# BahceKontrol.net
KiCad netlist of a schematic drawn in EAGLE
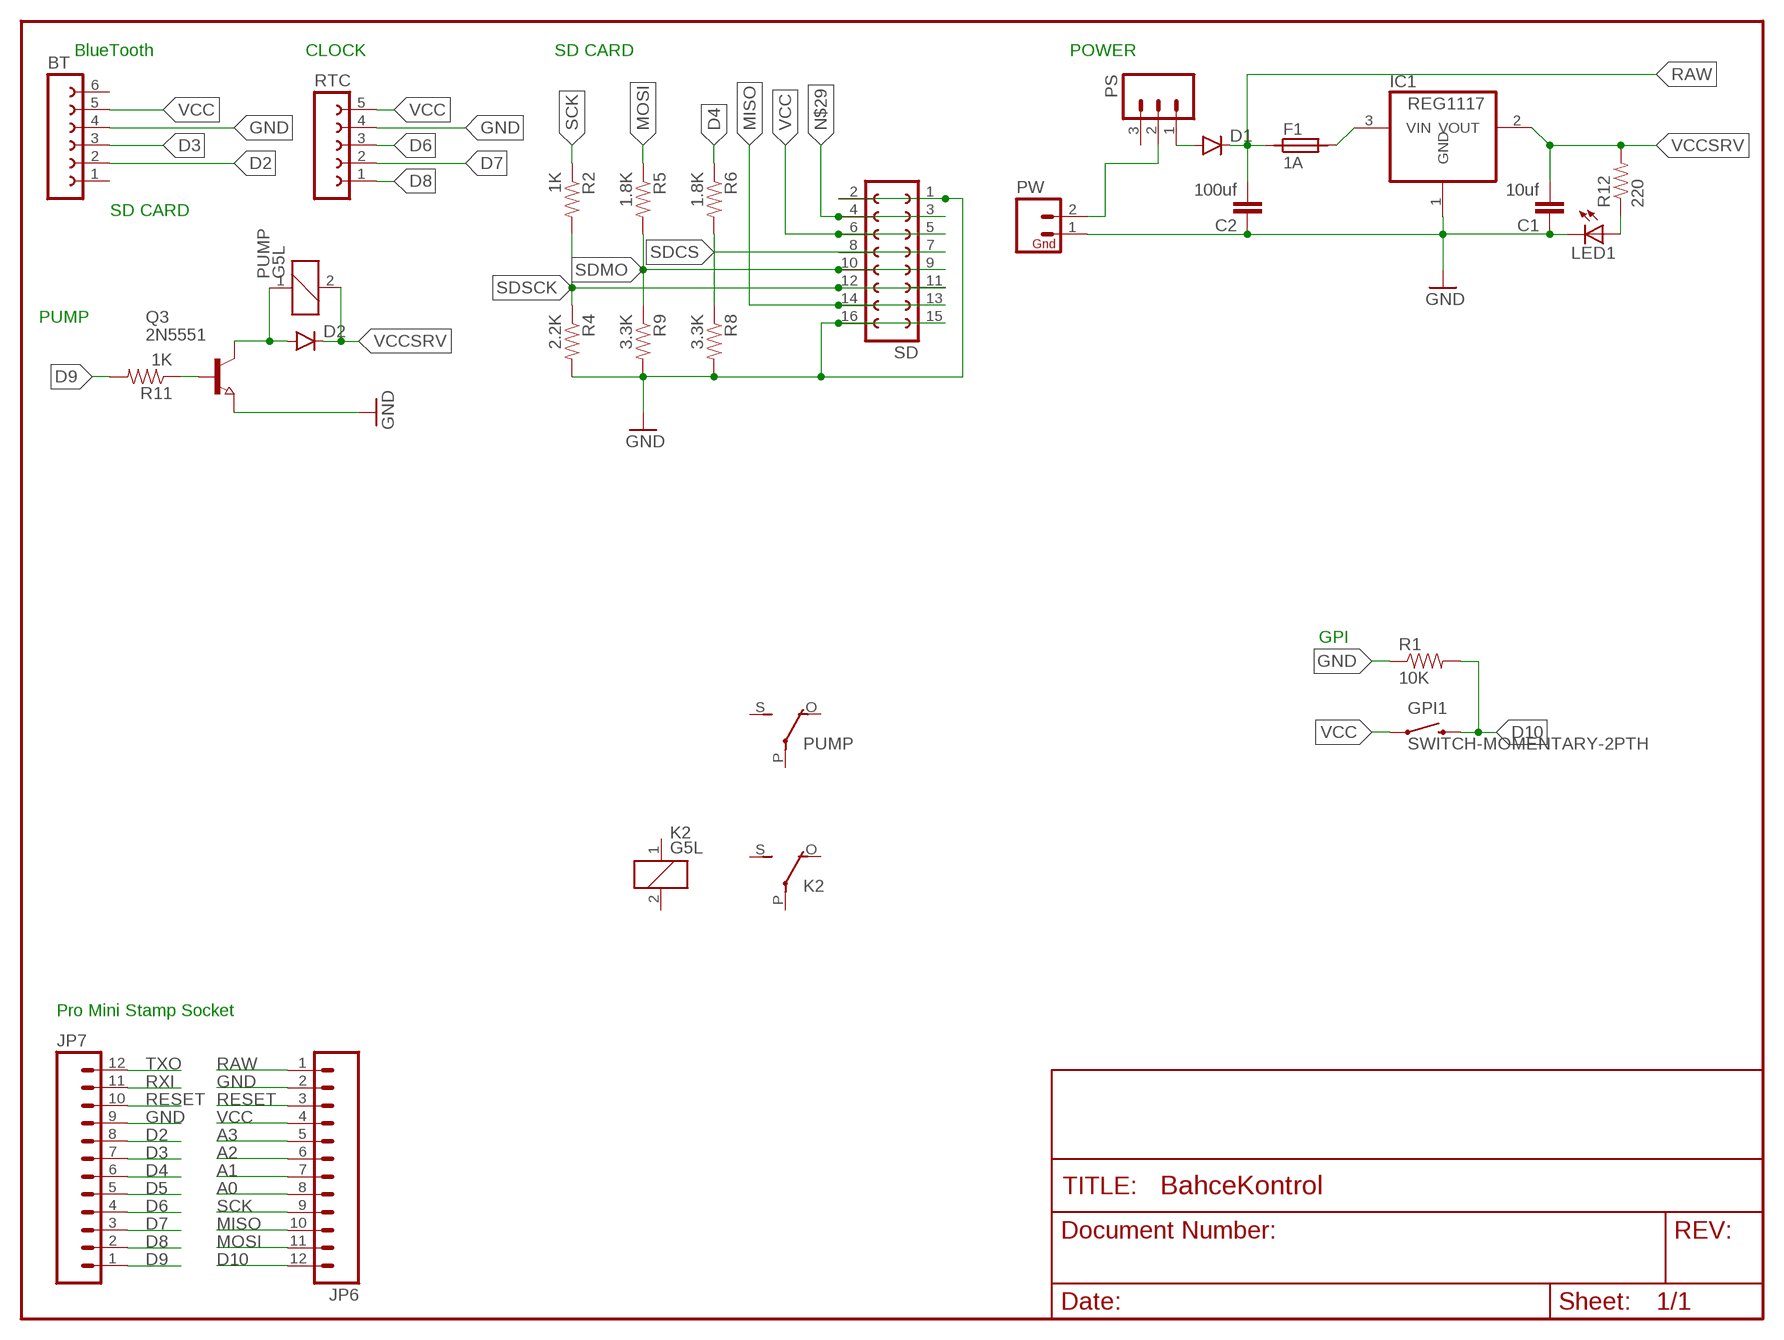
[diagram p0: schematic, sheet 1]

(export (version "E")
  (design (tool "Eeschema 10.0.6"))
  (components
    (comp (ref "BT")
      (value "FE06-1")
      (footprint "eagle-import:FE06")
      (libsource (lib "eagle-import") (part "FE06-1"))
    )
    (comp (ref "C1")
      (value "10uf")
      (footprint "eagle-import:0805")
      (libsource (lib "eagle-import") (part "CAP0805"))
    )
    (comp (ref "C2")
      (value "100uf")
      (footprint "eagle-import:0805")
      (libsource (lib "eagle-import") (part "CAP0805"))
    )
    (comp (ref "D1")
      (value "DIODESMA")
      (footprint "eagle-import:SMA-DIODE")
      (libsource (lib "eagle-import") (part "DIODESMA"))
    )
    (comp (ref "D2")
      (value "DIODESMA")
      (footprint "eagle-import:SMA-DIODE")
      (libsource (lib "eagle-import") (part "DIODESMA"))
    )
    (comp (ref "F1")
      (value "1A")
      (footprint "eagle-import:1820")
      (libsource (lib "eagle-import") (part "SIBA194600"))
    )
    (comp (ref "GPI1")
      (value "SWITCH-MOMENTARY-2PTH")
      (footprint "eagle-import:TACTILE-PTH")
      (libsource (lib "eagle-import") (part "SWITCH-MOMENTARY-2PTH"))
    )
    (comp (ref "IC1")
      (value "REG1117")
      (footprint "eagle-import:SOT223")
      (libsource (lib "eagle-import") (part "REG1117"))
    )
    (comp (ref "JP6")
      (value "M12PTH")
      (footprint "eagle-import:1X12")
      (libsource (lib "eagle-import") (part "M12PTH"))
    )
    (comp (ref "JP7")
      (value "M12PTH")
      (footprint "eagle-import:1X12")
      (libsource (lib "eagle-import") (part "M12PTH"))
    )
    (comp (ref "K2")
      (value "G5L")
      (footprint "eagle-import:G5LE")
      (libsource (lib "eagle-import") (part "G5L"))
    )
    (comp (ref "LED1")
      (value "LEDCHIP-LED0805")
      (footprint "eagle-import:CHIP-LED0805")
      (libsource (lib "eagle-import") (part "LEDCHIP-LED0805"))
    )
    (comp (ref "PS")
      (value "M03PTH")
      (footprint "eagle-import:1X03")
      (libsource (lib "eagle-import") (part "M03PTH"))
    )
    (comp (ref "PUMP")
      (value "G5L")
      (footprint "eagle-import:G5LE")
      (libsource (lib "eagle-import") (part "G5L"))
    )
    (comp (ref "PW")
      (value "M02PTH")
      (footprint "eagle-import:1X02")
      (libsource (lib "eagle-import") (part "M02PTH"))
    )
    (comp (ref "Q3")
      (value "2N5551")
      (footprint "eagle-import:SOT23")
      (libsource (lib "eagle-import") (part "NPN-TRANSISTOR_SOT23"))
    )
    (comp (ref "R1")
      (value "10K")
      (footprint "eagle-import:0805")
      (libsource (lib "eagle-import") (part "RESISTOR0805-RES"))
    )
    (comp (ref "R2")
      (value "1K")
      (footprint "eagle-import:0805")
      (libsource (lib "eagle-import") (part "RESISTOR0805-RES"))
    )
    (comp (ref "R4")
      (value "2.2K")
      (footprint "eagle-import:0805")
      (libsource (lib "eagle-import") (part "RESISTOR0805-RES"))
    )
    (comp (ref "R5")
      (value "1.8K")
      (footprint "eagle-import:0805")
      (libsource (lib "eagle-import") (part "RESISTOR0805-RES"))
    )
    (comp (ref "R6")
      (value "1.8K")
      (footprint "eagle-import:0805")
      (libsource (lib "eagle-import") (part "RESISTOR0805-RES"))
    )
    (comp (ref "R8")
      (value "3.3K")
      (footprint "eagle-import:0805")
      (libsource (lib "eagle-import") (part "RESISTOR0805-RES"))
    )
    (comp (ref "R9")
      (value "3.3K")
      (footprint "eagle-import:0805")
      (libsource (lib "eagle-import") (part "RESISTOR0805-RES"))
    )
    (comp (ref "R11")
      (value "1K")
      (footprint "eagle-import:0805")
      (libsource (lib "eagle-import") (part "RESISTOR0805-RES"))
    )
    (comp (ref "R12")
      (value "220")
      (footprint "eagle-import:0805")
      (libsource (lib "eagle-import") (part "RESISTOR0805-RES"))
    )
    (comp (ref "RTC")
      (value "FE05-1")
      (footprint "eagle-import:FE05-1")
      (libsource (lib "eagle-import") (part "FE05-1"))
    )
    (comp (ref "SD")
      (value "FE08-2")
      (footprint "eagle-import:FE08-2")
      (libsource (lib "eagle-import") (part "FE08-2"))
    )
  )
  (nets
    (net (code "1") (name "/A0") (class "Default")
      (node (ref "JP6") (pin "8") (pinfunction "8_8") (pintype "passive"))
    )
    (net (code "2") (name "/A1") (class "Default")
      (node (ref "JP6") (pin "7") (pinfunction "7_7") (pintype "passive"))
    )
    (net (code "3") (name "/A2") (class "Default")
      (node (ref "JP6") (pin "6") (pinfunction "6_6") (pintype "passive"))
    )
    (net (code "4") (name "/A3") (class "Default")
      (node (ref "JP6") (pin "5") (pinfunction "5_5") (pintype "passive"))
    )
    (net (code "5") (name "/D5") (class "Default")
      (node (ref "JP7") (pin "5") (pinfunction "5_5") (pintype "passive"))
    )
    (net (code "6") (name "/RESET") (class "Default")
      (node (ref "JP6") (pin "3") (pinfunction "3_3") (pintype "passive"))
      (node (ref "JP7") (pin "10") (pinfunction "10_10") (pintype "passive"))
    )
    (net (code "7") (name "/RXI") (class "Default")
      (node (ref "JP7") (pin "11") (pinfunction "11_11") (pintype "passive"))
    )
    (net (code "8") (name "/TXO") (class "Default")
      (node (ref "JP7") (pin "12") (pinfunction "12_12") (pintype "passive"))
    )
    (net (code "9") (name "D2") (class "Default")
      (node (ref "BT") (pin "2") (pinfunction "2_2") (pintype "passive"))
      (node (ref "JP7") (pin "8") (pinfunction "8_8") (pintype "passive"))
    )
    (net (code "10") (name "D3") (class "Default")
      (node (ref "BT") (pin "3") (pinfunction "3_3") (pintype "passive"))
      (node (ref "JP7") (pin "7") (pinfunction "7_7") (pintype "passive"))
    )
    (net (code "11") (name "D4") (class "Default")
      (node (ref "JP7") (pin "6") (pinfunction "6_6") (pintype "passive"))
      (node (ref "R6") (pin "1") (pinfunction "1_1") (pintype "passive"))
    )
    (net (code "12") (name "D6") (class "Default")
      (node (ref "JP7") (pin "4") (pinfunction "4_4") (pintype "passive"))
      (node (ref "RTC") (pin "3") (pinfunction "3_3") (pintype "passive"))
    )
    (net (code "13") (name "D7") (class "Default")
      (node (ref "JP7") (pin "3") (pinfunction "3_3") (pintype "passive"))
      (node (ref "RTC") (pin "2") (pinfunction "2_2") (pintype "passive"))
    )
    (net (code "14") (name "D8") (class "Default")
      (node (ref "JP7") (pin "2") (pinfunction "2_2") (pintype "passive"))
      (node (ref "RTC") (pin "1") (pinfunction "1_1") (pintype "passive"))
    )
    (net (code "15") (name "D9") (class "Default")
      (node (ref "JP7") (pin "1") (pinfunction "1_1") (pintype "passive"))
      (node (ref "R11") (pin "2") (pinfunction "2_2") (pintype "passive"))
    )
    (net (code "16") (name "D10") (class "Default")
      (node (ref "GPI1") (pin "3") (pinfunction "2_3") (pintype "passive"))
      (node (ref "JP6") (pin "12") (pinfunction "12_12") (pintype "passive"))
      (node (ref "R1") (pin "2") (pinfunction "2_2") (pintype "passive"))
    )
    (net (code "17") (name "GND") (class "Default")
      (node (ref "BT") (pin "4") (pinfunction "4_4") (pintype "passive"))
      (node (ref "C1") (pin "1") (pinfunction "1_1") (pintype "passive"))
      (node (ref "C2") (pin "1") (pinfunction "1_1") (pintype "passive"))
      (node (ref "IC1") (pin "1") (pinfunction "GND_1") (pintype "power_in"))
      (node (ref "JP6") (pin "2") (pinfunction "2_2") (pintype "passive"))
      (node (ref "JP7") (pin "9") (pinfunction "9_9") (pintype "passive"))
      (node (ref "LED1") (pin "C") (pinfunction "C_C") (pintype "passive"))
      (node (ref "PW") (pin "1") (pinfunction "1_1") (pintype "passive"))
      (node (ref "Q3") (pin "2") (pinfunction "E_2") (pintype "passive"))
      (node (ref "R1") (pin "1") (pinfunction "1_1") (pintype "passive"))
      (node (ref "R4") (pin "2") (pinfunction "2_2") (pintype "passive"))
      (node (ref "R8") (pin "2") (pinfunction "2_2") (pintype "passive"))
      (node (ref "R9") (pin "2") (pinfunction "2_2") (pintype "passive"))
      (node (ref "RTC") (pin "4") (pinfunction "4_4") (pintype "passive"))
      (node (ref "SD") (pin "1") (pinfunction "1_1") (pintype "passive"))
      (node (ref "SD") (pin "15") (pinfunction "15_15") (pintype "passive"))
      (node (ref "SD") (pin "16") (pinfunction "16_16") (pintype "passive"))
      (node (ref "SD") (pin "2") (pinfunction "2_2") (pintype "passive"))
    )
    (net (code "18") (name "MISO") (class "Default")
      (node (ref "JP6") (pin "10") (pinfunction "10_10") (pintype "passive"))
      (node (ref "SD") (pin "13") (pinfunction "13_13") (pintype "passive"))
      (node (ref "SD") (pin "14") (pinfunction "14_14") (pintype "passive"))
    )
    (net (code "19") (name "MOSI") (class "Default")
      (node (ref "JP6") (pin "11") (pinfunction "11_11") (pintype "passive"))
      (node (ref "R5") (pin "1") (pinfunction "1_1") (pintype "passive"))
    )
    (net (code "20") (name "N$29") (class "Default")
      (node (ref "SD") (pin "3") (pinfunction "3_3") (pintype "passive"))
      (node (ref "SD") (pin "4") (pinfunction "4_4") (pintype "passive"))
    )
    (net (code "21") (name "Net-(D1-PadA)") (class "Default")
      (node (ref "D1") (pin "A") (pinfunction "A_A") (pintype "passive"))
      (node (ref "PS") (pin "1") (pinfunction "1_1") (pintype "passive"))
    )
    (net (code "22") (name "Net-(IC1-VIN)") (class "Default")
      (node (ref "F1") (pin "2") (pinfunction "2_2") (pintype "passive"))
      (node (ref "IC1") (pin "3") (pinfunction "VIN_3") (pintype "input"))
    )
    (net (code "23") (name "Net-(LED1-PadA)") (class "Default")
      (node (ref "LED1") (pin "A") (pinfunction "A_A") (pintype "passive"))
      (node (ref "R12") (pin "1") (pinfunction "1_1") (pintype "passive"))
    )
    (net (code "24") (name "Net-(PS-Pad2)") (class "Default")
      (node (ref "PS") (pin "2") (pinfunction "2_2") (pintype "passive"))
      (node (ref "PW") (pin "2") (pinfunction "2_2") (pintype "passive"))
    )
    (net (code "25") (name "Net-(Q3-B)") (class "Default")
      (node (ref "Q3") (pin "1") (pinfunction "B_1") (pintype "passive"))
      (node (ref "R11") (pin "1") (pinfunction "1_1") (pintype "passive"))
    )
    (net (code "26") (name "Net-(Q3-C)") (class "Default")
      (node (ref "D2") (pin "A") (pinfunction "A_A") (pintype "passive"))
      (node (ref "PUMP") (pin "1") (pinfunction "1_1") (pintype "passive"))
      (node (ref "Q3") (pin "3") (pinfunction "C_3") (pintype "passive"))
    )
    (net (code "27") (name "RAW") (class "Default")
      (node (ref "C2") (pin "2") (pinfunction "2_2") (pintype "passive"))
      (node (ref "D1") (pin "C") (pinfunction "C_C") (pintype "passive"))
      (node (ref "F1") (pin "1") (pinfunction "1_1") (pintype "passive"))
      (node (ref "JP6") (pin "1") (pinfunction "1_1") (pintype "passive"))
    )
    (net (code "28") (name "SCK") (class "Default")
      (node (ref "JP6") (pin "9") (pinfunction "9_9") (pintype "passive"))
      (node (ref "R2") (pin "1") (pinfunction "1_1") (pintype "passive"))
    )
    (net (code "29") (name "SDCS") (class "Default")
      (node (ref "R6") (pin "2") (pinfunction "2_2") (pintype "passive"))
      (node (ref "R8") (pin "1") (pinfunction "1_1") (pintype "passive"))
      (node (ref "SD") (pin "7") (pinfunction "7_7") (pintype "passive"))
      (node (ref "SD") (pin "8") (pinfunction "8_8") (pintype "passive"))
    )
    (net (code "30") (name "SDMO") (class "Default")
      (node (ref "R5") (pin "2") (pinfunction "2_2") (pintype "passive"))
      (node (ref "R9") (pin "1") (pinfunction "1_1") (pintype "passive"))
      (node (ref "SD") (pin "10") (pinfunction "10_10") (pintype "passive"))
      (node (ref "SD") (pin "9") (pinfunction "9_9") (pintype "passive"))
    )
    (net (code "31") (name "SDSCK") (class "Default")
      (node (ref "R2") (pin "2") (pinfunction "2_2") (pintype "passive"))
      (node (ref "R4") (pin "1") (pinfunction "1_1") (pintype "passive"))
      (node (ref "SD") (pin "11") (pinfunction "11_11") (pintype "passive"))
      (node (ref "SD") (pin "12") (pinfunction "12_12") (pintype "passive"))
    )
    (net (code "32") (name "VCC") (class "Default")
      (node (ref "BT") (pin "5") (pinfunction "5_5") (pintype "passive"))
      (node (ref "GPI1") (pin "1") (pinfunction "1_1") (pintype "passive"))
      (node (ref "JP6") (pin "4") (pinfunction "4_4") (pintype "passive"))
      (node (ref "RTC") (pin "5") (pinfunction "5_5") (pintype "passive"))
      (node (ref "SD") (pin "5") (pinfunction "5_5") (pintype "passive"))
      (node (ref "SD") (pin "6") (pinfunction "6_6") (pintype "passive"))
    )
    (net (code "33") (name "VCCSRV") (class "Default")
      (node (ref "C1") (pin "2") (pinfunction "2_2") (pintype "passive"))
      (node (ref "D2") (pin "C") (pinfunction "C_C") (pintype "passive"))
      (node (ref "IC1") (pin "2") (pinfunction "VOUT_2") (pintype "output"))
      (node (ref "PUMP") (pin "2") (pinfunction "2_2") (pintype "passive"))
      (node (ref "R12") (pin "2") (pinfunction "2_2") (pintype "passive"))
    )
    (net (code "34") (name "unconnected-(BT-Pad1)") (class "Default")
      (node (ref "BT") (pin "1") (pinfunction "1_1") (pintype "passive"))
    )
    (net (code "35") (name "unconnected-(BT-Pad6)") (class "Default")
      (node (ref "BT") (pin "6") (pinfunction "6_6") (pintype "passive"))
    )
    (net (code "36") (name "unconnected-(K2-Pad1)") (class "Default")
      (node (ref "K2") (pin "1") (pinfunction "1_1") (pintype "passive"))
    )
    (net (code "37") (name "unconnected-(K2-Pad2)") (class "Default")
      (node (ref "K2") (pin "2") (pinfunction "2_2") (pintype "passive"))
    )
    (net (code "38") (name "unconnected-(K2-PadO)") (class "Default")
      (node (ref "K2") (pin "O") (pinfunction "O_O") (pintype "passive"))
    )
    (net (code "39") (name "unconnected-(K2-PadP)") (class "Default")
      (node (ref "K2") (pin "P") (pinfunction "P_P") (pintype "passive"))
    )
    (net (code "40") (name "unconnected-(K2-PadS)") (class "Default")
      (node (ref "K2") (pin "S") (pinfunction "S_S") (pintype "passive"))
    )
    (net (code "41") (name "unconnected-(PS-Pad3)") (class "Default")
      (node (ref "PS") (pin "3") (pinfunction "3_3") (pintype "passive"))
    )
    (net (code "42") (name "unconnected-(PUMP-PadO)") (class "Default")
      (node (ref "PUMP") (pin "O") (pinfunction "O_O") (pintype "passive"))
    )
    (net (code "43") (name "unconnected-(PUMP-PadP)") (class "Default")
      (node (ref "PUMP") (pin "P") (pinfunction "P_P") (pintype "passive"))
    )
    (net (code "44") (name "unconnected-(PUMP-PadS)") (class "Default")
      (node (ref "PUMP") (pin "S") (pinfunction "S_S") (pintype "passive"))
    )
  )
)
